# jt-100.net
KiCad netlist of a schematic drawn in EAGLE
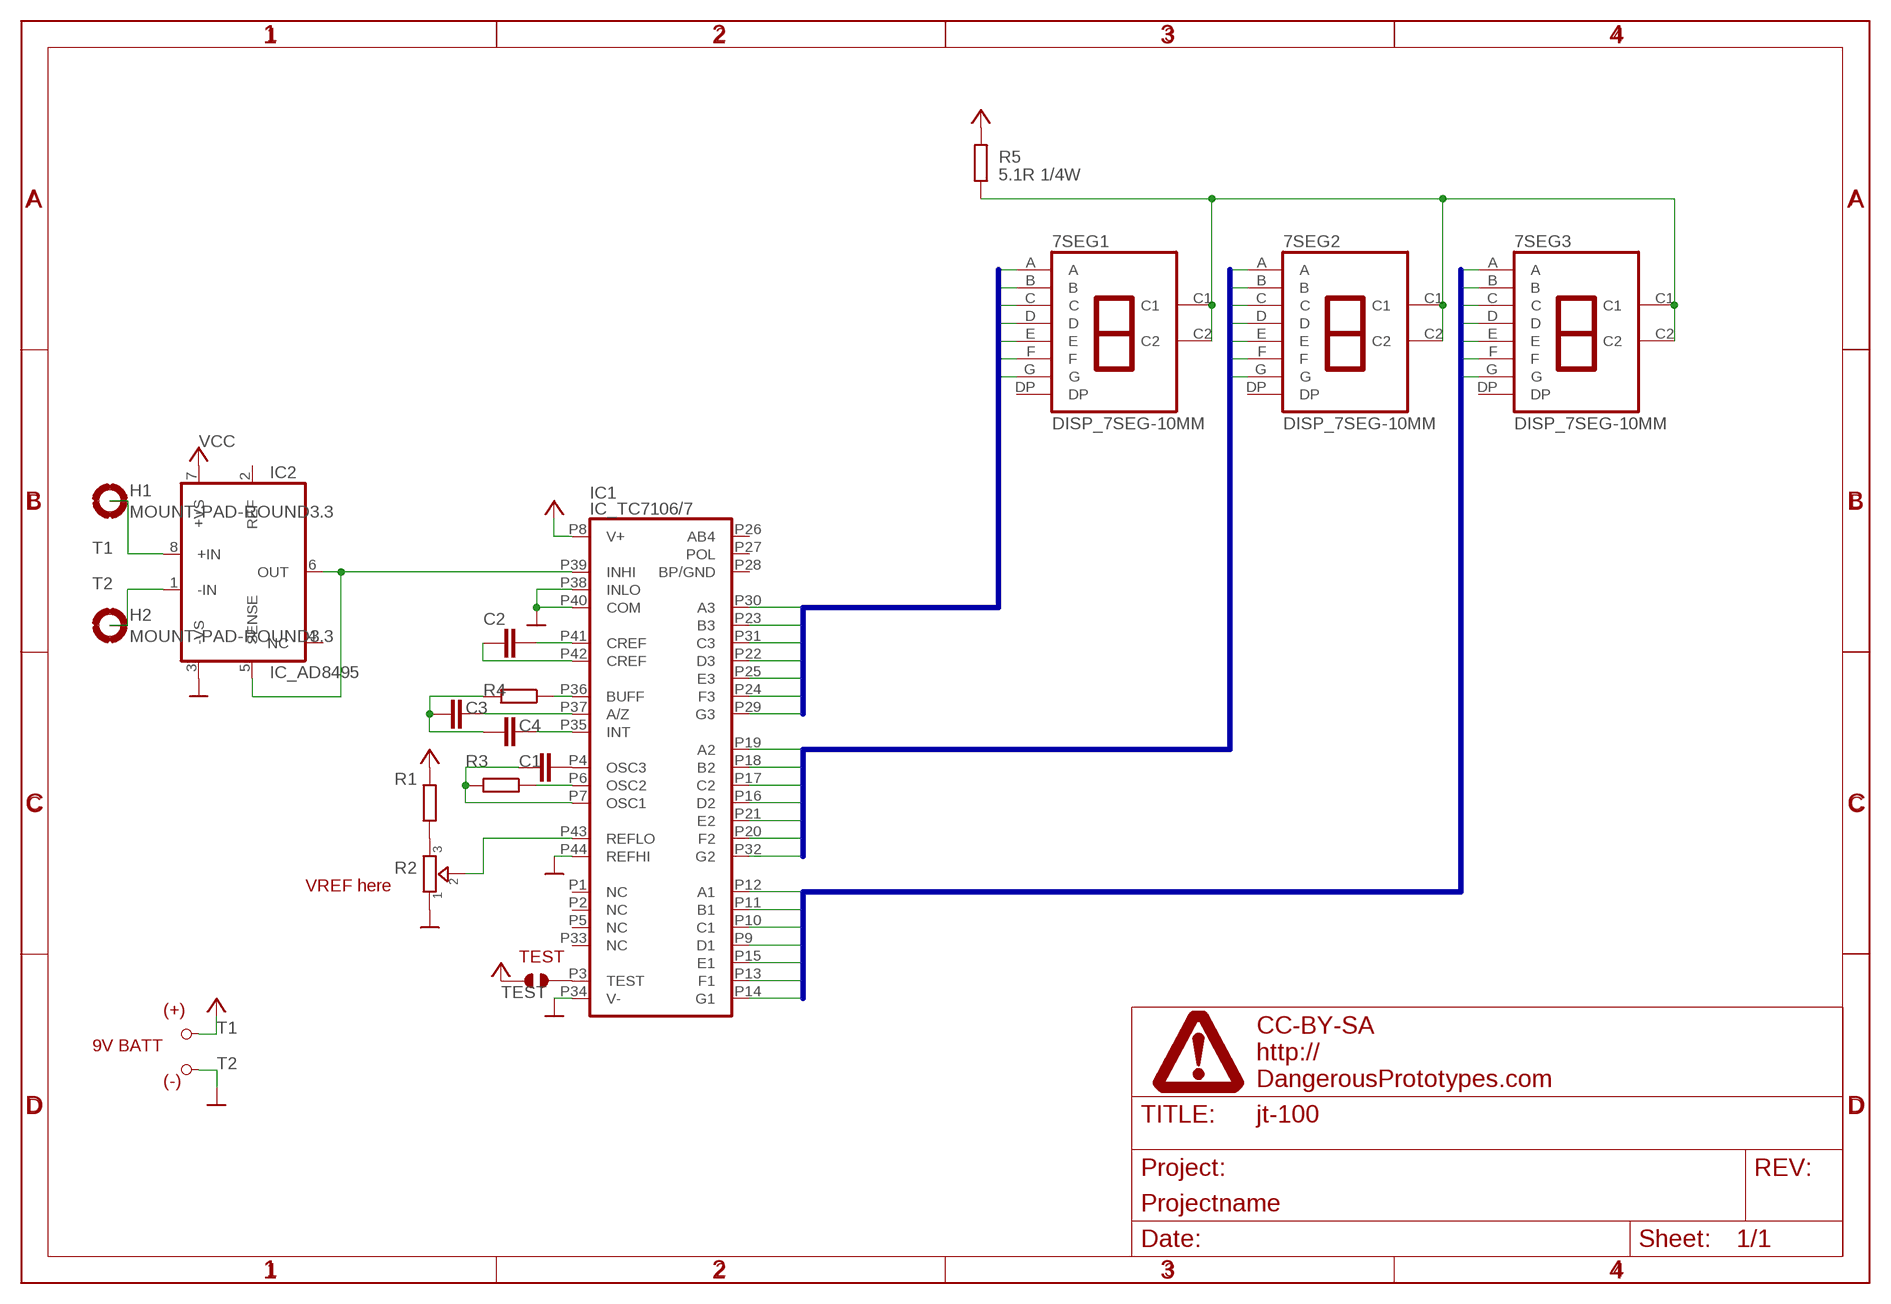
[diagram p0: schematic, sheet 1]

(export (version "E")
  (design (tool "Eeschema 10.0.6"))
  (components
    (comp (ref "7SEG1")
      (value "DISP_7SEG-10MM")
      (footprint "eagle-import:DISP_7SEG_KTS_4817CKR-P")
      (fields (field (name "MPN") "LTS-4817CKR-P"))
      (libsource (lib "eagle-import") (part "DISP_7SEG-10MM"))
    )
    (comp (ref "7SEG2")
      (value "DISP_7SEG-10MM")
      (footprint "eagle-import:DISP_7SEG_KTS_4817CKR-P")
      (fields (field (name "MPN") "LTS-4817CKR-P"))
      (libsource (lib "eagle-import") (part "DISP_7SEG-10MM"))
    )
    (comp (ref "7SEG3")
      (value "DISP_7SEG-10MM")
      (footprint "eagle-import:DISP_7SEG_KTS_4817CKR-P")
      (fields (field (name "MPN") "LTS-4817CKR-P"))
      (libsource (lib "eagle-import") (part "DISP_7SEG-10MM"))
    )
    (comp (ref "C1")
      (value "CAPACITOR_NPOL-1206")
      (footprint "eagle-import:C1206")
      (libsource (lib "eagle-import") (part "CAPACITOR_NPOL-1206"))
    )
    (comp (ref "C2")
      (value "CAPACITOR_NPOL-1206")
      (footprint "eagle-import:C1206")
      (libsource (lib "eagle-import") (part "CAPACITOR_NPOL-1206"))
    )
    (comp (ref "C3")
      (value "CAPACITOR_NPOL-1206")
      (footprint "eagle-import:C1206")
      (libsource (lib "eagle-import") (part "CAPACITOR_NPOL-1206"))
    )
    (comp (ref "C4")
      (value "CAPACITOR_NPOL-1206")
      (footprint "eagle-import:C1206")
      (libsource (lib "eagle-import") (part "CAPACITOR_NPOL-1206"))
    )
    (comp (ref "H1")
      (value "MOUNT-PAD-ROUND3.3")
      (footprint "eagle-import:3,3-PAD")
      (libsource (lib "eagle-import") (part "MOUNT-PAD-ROUND3.3"))
    )
    (comp (ref "H2")
      (value "MOUNT-PAD-ROUND3.3")
      (footprint "eagle-import:3,3-PAD")
      (libsource (lib "eagle-import") (part "MOUNT-PAD-ROUND3.3"))
    )
    (comp (ref "IC1")
      (value "IC_TC7106/7")
      (footprint "eagle-import:TQFP-44")
      (fields (field (name "MPN") "TC7106CKW"))
      (libsource (lib "eagle-import") (part "IC_TC7106/7"))
    )
    (comp (ref "IC2")
      (value "IC_AD8495")
      (footprint "eagle-import:MSOP8")
      (fields (field (name "MPN") "AD8495ARMZ"))
      (libsource (lib "eagle-import") (part "IC_AD8495"))
    )
    (comp (ref "R1")
      (value "RESISTOR-1206")
      (footprint "eagle-import:R1206")
      (libsource (lib "eagle-import") (part "RESISTOR-1206"))
    )
    (comp (ref "R2")
      (value "TRIMMER-3314G")
      (footprint "eagle-import:TRIMMER_3314G")
      (libsource (lib "eagle-import") (part "TRIMMER-3314G"))
    )
    (comp (ref "R3")
      (value "RESISTOR-1206")
      (footprint "eagle-import:R1206")
      (libsource (lib "eagle-import") (part "RESISTOR-1206"))
    )
    (comp (ref "R4")
      (value "RESISTOR-1206")
      (footprint "eagle-import:R1206")
      (libsource (lib "eagle-import") (part "RESISTOR-1206"))
    )
    (comp (ref "R5")
      (value "5.1R 1/4W")
      (footprint "eagle-import:R1206")
      (libsource (lib "eagle-import") (part "RESISTOR-1206"))
    )
    (comp (ref "T1")
      (value "PAD_TERMINAL-1.02MM_SQUARE")
      (footprint "eagle-import:CON_PAD_SQUARE_1.02MM")
      (libsource (lib "eagle-import") (part "PAD_TERMINAL-1.02MM_SQUARE"))
    )
    (comp (ref "T2")
      (value "PAD_TERMINAL-1.02MM_ROUND")
      (footprint "eagle-import:CON_PAD_ROUND_1.02MM")
      (libsource (lib "eagle-import") (part "PAD_TERMINAL-1.02MM_ROUND"))
    )
    (comp (ref "TEST")
      (value "JUMPER_SOLDER_1X2")
      (footprint "eagle-import:JUMPER_SOLDER_1X2")
      (libsource (lib "eagle-import") (part "JUMPER_SOLDER_1X2"))
    )
    (comp (ref "U$1")
      (value "FRAME_DINA4_L")
      (footprint "eagle-import:DP_LOGO")
      (libsource (lib "eagle-import") (part "FRAME_DINA4_L"))
    )
  )
  (nets
    (net (code "1") (name "/1S1") (class "Default")
      (node (ref "7SEG3") (pin "A") (pinfunction "A_A") (pintype "bidirectional"))
      (node (ref "IC1") (pin "P12") (pinfunction "A1_P12") (pintype "bidirectional"))
    )
    (net (code "2") (name "/1S2") (class "Default")
      (node (ref "7SEG3") (pin "B") (pinfunction "B_B") (pintype "bidirectional"))
      (node (ref "IC1") (pin "P11") (pinfunction "B1_P11") (pintype "bidirectional"))
    )
    (net (code "3") (name "/1S3") (class "Default")
      (node (ref "7SEG3") (pin "C") (pinfunction "C_C") (pintype "bidirectional"))
      (node (ref "IC1") (pin "P10") (pinfunction "C1_P10") (pintype "bidirectional"))
    )
    (net (code "4") (name "/1S4") (class "Default")
      (node (ref "7SEG3") (pin "D") (pinfunction "D_D") (pintype "bidirectional"))
      (node (ref "IC1") (pin "P9") (pinfunction "D1_P9") (pintype "bidirectional"))
    )
    (net (code "5") (name "/1S5") (class "Default")
      (node (ref "7SEG3") (pin "E") (pinfunction "E_E") (pintype "bidirectional"))
      (node (ref "IC1") (pin "P15") (pinfunction "E1_P15") (pintype "bidirectional"))
    )
    (net (code "6") (name "/1S6") (class "Default")
      (node (ref "7SEG3") (pin "F") (pinfunction "F_F") (pintype "bidirectional"))
      (node (ref "IC1") (pin "P13") (pinfunction "F1_P13") (pintype "bidirectional"))
    )
    (net (code "7") (name "/1S7") (class "Default")
      (node (ref "7SEG3") (pin "G") (pinfunction "G_G") (pintype "bidirectional"))
      (node (ref "IC1") (pin "P14") (pinfunction "G1_P14") (pintype "bidirectional"))
    )
    (net (code "8") (name "/10S1") (class "Default")
      (node (ref "7SEG2") (pin "A") (pinfunction "A_A") (pintype "bidirectional"))
      (node (ref "IC1") (pin "P19") (pinfunction "A2_P19") (pintype "input"))
    )
    (net (code "9") (name "/10S2") (class "Default")
      (node (ref "7SEG2") (pin "B") (pinfunction "B_B") (pintype "bidirectional"))
      (node (ref "IC1") (pin "P18") (pinfunction "B2_P18") (pintype "input"))
    )
    (net (code "10") (name "/10S3") (class "Default")
      (node (ref "7SEG2") (pin "C") (pinfunction "C_C") (pintype "bidirectional"))
      (node (ref "IC1") (pin "P17") (pinfunction "C2_P17") (pintype "input"))
    )
    (net (code "11") (name "/10S4") (class "Default")
      (node (ref "7SEG2") (pin "D") (pinfunction "D_D") (pintype "bidirectional"))
      (node (ref "IC1") (pin "P16") (pinfunction "D2_P16") (pintype "bidirectional"))
    )
    (net (code "12") (name "/10S5") (class "Default")
      (node (ref "7SEG2") (pin "E") (pinfunction "E_E") (pintype "bidirectional"))
      (node (ref "IC1") (pin "P21") (pinfunction "E2_P21") (pintype "input"))
    )
    (net (code "13") (name "/10S6") (class "Default")
      (node (ref "7SEG2") (pin "F") (pinfunction "F_F") (pintype "bidirectional"))
      (node (ref "IC1") (pin "P20") (pinfunction "F2_P20") (pintype "input"))
    )
    (net (code "14") (name "/10S7") (class "Default")
      (node (ref "7SEG2") (pin "G") (pinfunction "G_G") (pintype "bidirectional"))
      (node (ref "IC1") (pin "P32") (pinfunction "G2_P32") (pintype "input"))
    )
    (net (code "15") (name "/100S1") (class "Default")
      (node (ref "7SEG1") (pin "A") (pinfunction "A_A") (pintype "bidirectional"))
      (node (ref "IC1") (pin "P30") (pinfunction "A3_P30") (pintype "input"))
    )
    (net (code "16") (name "/100S2") (class "Default")
      (node (ref "7SEG1") (pin "B") (pinfunction "B_B") (pintype "bidirectional"))
      (node (ref "IC1") (pin "P23") (pinfunction "B3_P23") (pintype "input"))
    )
    (net (code "17") (name "/100S3") (class "Default")
      (node (ref "7SEG1") (pin "C") (pinfunction "C_C") (pintype "bidirectional"))
      (node (ref "IC1") (pin "P31") (pinfunction "C3_P31") (pintype "input"))
    )
    (net (code "18") (name "/100S4") (class "Default")
      (node (ref "7SEG1") (pin "D") (pinfunction "D_D") (pintype "bidirectional"))
      (node (ref "IC1") (pin "P22") (pinfunction "D3_P22") (pintype "input"))
    )
    (net (code "19") (name "/100S5") (class "Default")
      (node (ref "7SEG1") (pin "E") (pinfunction "E_E") (pintype "bidirectional"))
      (node (ref "IC1") (pin "P25") (pinfunction "E3_P25") (pintype "input"))
    )
    (net (code "20") (name "/100S6") (class "Default")
      (node (ref "7SEG1") (pin "F") (pinfunction "F_F") (pintype "bidirectional"))
      (node (ref "IC1") (pin "P24") (pinfunction "F3_P24") (pintype "input"))
    )
    (net (code "21") (name "/100S7") (class "Default")
      (node (ref "7SEG1") (pin "G") (pinfunction "G_G") (pintype "bidirectional"))
      (node (ref "IC1") (pin "P29") (pinfunction "G3_P29") (pintype "input"))
    )
    (net (code "22") (name "/T1") (class "Default")
      (node (ref "H1") (pin "B3,3") (pinfunction "MOUNT_B3,3") (pintype "passive"))
      (node (ref "IC2") (pin "8") (pinfunction "+IN_8") (pintype "input"))
    )
    (net (code "23") (name "/T2") (class "Default")
      (node (ref "H2") (pin "B3,3") (pinfunction "MOUNT_B3,3") (pintype "passive"))
      (node (ref "IC2") (pin "1") (pinfunction "-IN_1") (pintype "input"))
    )
    (net (code "24") (name "Net-(7SEG1-PadC1)") (class "Default")
      (node (ref "7SEG1") (pin "C1") (pinfunction "C1_C1") (pintype "bidirectional"))
      (node (ref "7SEG1") (pin "C2") (pinfunction "C2_C2") (pintype "bidirectional"))
      (node (ref "7SEG2") (pin "C1") (pinfunction "C1_C1") (pintype "bidirectional"))
      (node (ref "7SEG2") (pin "C2") (pinfunction "C2_C2") (pintype "bidirectional"))
      (node (ref "7SEG3") (pin "C1") (pinfunction "C1_C1") (pintype "bidirectional"))
      (node (ref "7SEG3") (pin "C2") (pinfunction "C2_C2") (pintype "bidirectional"))
      (node (ref "R5") (pin "1") (pinfunction "1_1") (pintype "passive"))
    )
    (net (code "25") (name "Net-(C2-Pad1)") (class "Default")
      (node (ref "C2") (pin "1") (pinfunction "1_1") (pintype "passive"))
      (node (ref "IC1") (pin "P42") (pinfunction "CREF_P42") (pintype "input"))
    )
    (net (code "26") (name "Net-(C2-Pad2)") (class "Default")
      (node (ref "C2") (pin "2") (pinfunction "2_2") (pintype "passive"))
      (node (ref "IC1") (pin "P41") (pinfunction "CREF_P41") (pintype "input"))
    )
    (net (code "27") (name "Net-(C3-Pad1)") (class "Default")
      (node (ref "C3") (pin "1") (pinfunction "1_1") (pintype "passive"))
      (node (ref "C4") (pin "1") (pinfunction "1_1") (pintype "passive"))
      (node (ref "R4") (pin "2") (pinfunction "2_2") (pintype "passive"))
    )
    (net (code "28") (name "Net-(IC1-A{slash}Z)") (class "Default")
      (node (ref "C3") (pin "2") (pinfunction "2_2") (pintype "passive"))
      (node (ref "IC1") (pin "P37") (pinfunction "A/Z_P37") (pintype "input"))
    )
    (net (code "29") (name "Net-(IC1-BUFF)") (class "Default")
      (node (ref "IC1") (pin "P36") (pinfunction "BUFF_P36") (pintype "input"))
      (node (ref "R4") (pin "1") (pinfunction "1_1") (pintype "passive"))
    )
    (net (code "30") (name "Net-(IC1-INHI)") (class "Default")
      (node (ref "IC1") (pin "P39") (pinfunction "INHI_P39") (pintype "input"))
      (node (ref "IC2") (pin "5") (pinfunction "SENSE_5") (pintype "bidirectional"))
      (node (ref "IC2") (pin "6") (pinfunction "OUT_6") (pintype "output"))
    )
    (net (code "31") (name "Net-(IC1-INT)") (class "Default")
      (node (ref "C4") (pin "2") (pinfunction "2_2") (pintype "passive"))
      (node (ref "IC1") (pin "P35") (pinfunction "INT_P35") (pintype "input"))
    )
    (net (code "32") (name "Net-(IC1-OSC1)") (class "Default")
      (node (ref "C1") (pin "1") (pinfunction "1_1") (pintype "passive"))
      (node (ref "IC1") (pin "P7") (pinfunction "OSC1_P7") (pintype "bidirectional"))
      (node (ref "R3") (pin "2") (pinfunction "2_2") (pintype "passive"))
    )
    (net (code "33") (name "Net-(IC1-OSC2)") (class "Default")
      (node (ref "IC1") (pin "P6") (pinfunction "OSC2_P6") (pintype "bidirectional"))
      (node (ref "R3") (pin "1") (pinfunction "1_1") (pintype "passive"))
    )
    (net (code "34") (name "Net-(IC1-OSC3)") (class "Default")
      (node (ref "C1") (pin "2") (pinfunction "2_2") (pintype "passive"))
      (node (ref "IC1") (pin "P4") (pinfunction "OSC3_P4") (pintype "bidirectional"))
    )
    (net (code "35") (name "Net-(IC1-REFLO)") (class "Default")
      (node (ref "IC1") (pin "P43") (pinfunction "REFLO_P43") (pintype "input"))
      (node (ref "R2") (pin "2") (pinfunction "2_2") (pintype "passive"))
    )
    (net (code "36") (name "Net-(IC1-TEST)") (class "Default")
      (node (ref "IC1") (pin "P3") (pinfunction "TEST_P3") (pintype "bidirectional"))
      (node (ref "TEST") (pin "2") (pinfunction "2_2") (pintype "passive"))
    )
    (net (code "37") (name "Net-(R1-Pad1)") (class "Default")
      (node (ref "R1") (pin "1") (pinfunction "1_1") (pintype "passive"))
      (node (ref "R2") (pin "3") (pinfunction "3_3") (pintype "passive"))
    )
    (net (code "38") (name "SUPPLY_GND") (class "Default")
      (node (ref "IC1") (pin "P34") (pinfunction "V-_P34") (pintype "power_in"))
      (node (ref "IC1") (pin "P38") (pinfunction "INLO_P38") (pintype "input"))
      (node (ref "IC1") (pin "P40") (pinfunction "COM_P40") (pintype "input"))
      (node (ref "IC1") (pin "P44") (pinfunction "REFHI_P44") (pintype "input"))
      (node (ref "IC2") (pin "3") (pinfunction "-VS_3") (pintype "power_in"))
      (node (ref "R2") (pin "1") (pinfunction "1_1") (pintype "passive"))
      (node (ref "T2") (pin "P") (pinfunction "P_P") (pintype "passive"))
    )
    (net (code "39") (name "SUPPLY_VCC") (class "Default")
      (node (ref "IC1") (pin "P8") (pinfunction "V+_P8") (pintype "power_in"))
      (node (ref "IC2") (pin "7") (pinfunction "+VS_7") (pintype "power_in"))
      (node (ref "R1") (pin "2") (pinfunction "2_2") (pintype "passive"))
      (node (ref "R5") (pin "2") (pinfunction "2_2") (pintype "passive"))
      (node (ref "T1") (pin "P") (pinfunction "P_P") (pintype "passive"))
      (node (ref "TEST") (pin "1") (pinfunction "1_1") (pintype "passive"))
    )
    (net (code "40") (name "unconnected-(7SEG1-PadDP)") (class "Default")
      (node (ref "7SEG1") (pin "DP") (pinfunction "DP_DP") (pintype "bidirectional"))
    )
    (net (code "41") (name "unconnected-(7SEG2-PadDP)") (class "Default")
      (node (ref "7SEG2") (pin "DP") (pinfunction "DP_DP") (pintype "bidirectional"))
    )
    (net (code "42") (name "unconnected-(7SEG3-PadDP)") (class "Default")
      (node (ref "7SEG3") (pin "DP") (pinfunction "DP_DP") (pintype "bidirectional"))
    )
    (net (code "43") (name "unconnected-(IC1-AB4-PadP26)") (class "Default")
      (node (ref "IC1") (pin "P26") (pinfunction "AB4_P26") (pintype "input"))
    )
    (net (code "44") (name "unconnected-(IC1-BP{slash}GND-PadP28)") (class "Default")
      (node (ref "IC1") (pin "P28") (pinfunction "BP/GND_P28") (pintype "input"))
    )
    (net (code "45") (name "unconnected-(IC1-NC-PadP1)") (class "Default")
      (node (ref "IC1") (pin "P1") (pinfunction "NC_P1") (pintype "bidirectional"))
    )
    (net (code "46") (name "unconnected-(IC1-NC-PadP2)") (class "Default")
      (node (ref "IC1") (pin "P2") (pinfunction "NC_P2") (pintype "bidirectional"))
    )
    (net (code "47") (name "unconnected-(IC1-NC-PadP5)") (class "Default")
      (node (ref "IC1") (pin "P5") (pinfunction "NC_P5") (pintype "bidirectional"))
    )
    (net (code "48") (name "unconnected-(IC1-NC-PadP33)") (class "Default")
      (node (ref "IC1") (pin "P33") (pinfunction "NC_P33") (pintype "input"))
    )
    (net (code "49") (name "unconnected-(IC1-POL-PadP27)") (class "Default")
      (node (ref "IC1") (pin "P27") (pinfunction "POL_P27") (pintype "input"))
    )
    (net (code "50") (name "unconnected-(IC2-NC-Pad4)") (class "Default")
      (node (ref "IC2") (pin "4") (pinfunction "NC_4") (pintype "bidirectional"))
    )
    (net (code "51") (name "unconnected-(IC2-REF-Pad2)") (class "Default")
      (node (ref "IC2") (pin "2") (pinfunction "REF_2") (pintype "bidirectional"))
    )
  )
)
